# flash.net
KiCad netlist of a schematic drawn in Altium Designer
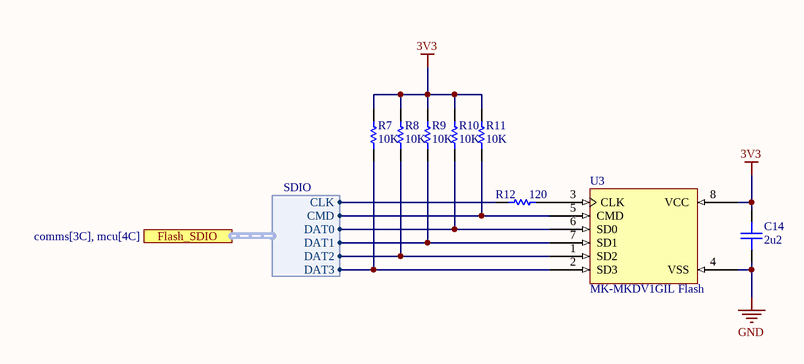
[diagram p0: flash.SchDoc]

(export (version "E")
  (design (tool "Eeschema 10.0.6"))
  (components
    (comp (ref "C14")
      (value "2u2")
      (description "Capacitor")
      (libsource (lib "drfc_schlib") (part "Capacitor"))
    )
    (comp (ref "R7") (value "10K") (description "Resistor") (libsource (lib "drfc_schlib") (part "Resistor")))
    (comp (ref "R8") (value "10K") (description "Resistor") (libsource (lib "drfc_schlib") (part "Resistor")))
    (comp (ref "R9") (value "10K") (description "Resistor") (libsource (lib "drfc_schlib") (part "Resistor")))
    (comp (ref "R10")
      (value "10K")
      (description "Resistor")
      (libsource (lib "drfc_schlib") (part "Resistor"))
    )
    (comp (ref "R11")
      (value "10K")
      (description "Resistor")
      (libsource (lib "drfc_schlib") (part "Resistor"))
    )
    (comp (ref "R12")
      (value "120")
      (description "Resistor")
      (libsource (lib "drfc_schlib") (part "Resistor"))
    )
    (comp (ref "U3")
      (value "MK-MKDV1GIL Flash")
      (description "1Gbit LGA-8(6x8) SD NAND FLASH ROHS")
      (libsource (lib "drfc_schlib") (part "MK-MKDV1GIL"))
    )
  )
  (nets
    (net (code "2") (name "/CLK") (class "Default")
      (node (ref "R12") (pin "2") (pinfunction "2_2") (pintype "passive"))
    )
    (net (code "3") (name "/CMD") (class "Default")
      (node (ref "R11") (pin "1") (pinfunction "1_1") (pintype "passive"))
      (node (ref "U3") (pin "5") (pinfunction "CMD_5") (pintype "input"))
    )
    (net (code "4") (name "/DAT0") (class "Default")
      (node (ref "R10") (pin "1") (pinfunction "1_1") (pintype "passive"))
      (node (ref "U3") (pin "6") (pinfunction "SD0_6") (pintype "input"))
    )
    (net (code "5") (name "/DAT1") (class "Default")
      (node (ref "R9") (pin "1") (pinfunction "1_1") (pintype "passive"))
      (node (ref "U3") (pin "7") (pinfunction "SD1_7") (pintype "input"))
    )
    (net (code "6") (name "/DAT2") (class "Default")
      (node (ref "R8") (pin "1") (pinfunction "1_1") (pintype "passive"))
      (node (ref "U3") (pin "1") (pinfunction "SD2_1") (pintype "input"))
    )
    (net (code "7") (name "/DAT3") (class "Default")
      (node (ref "R7") (pin "1") (pinfunction "1_1") (pintype "passive"))
      (node (ref "U3") (pin "2") (pinfunction "SD3_2") (pintype "input"))
    )
    (net (code "9") (name "3V3") (class "Default")
      (node (ref "C14") (pin "2") (pinfunction "2_2") (pintype "passive"))
      (node (ref "R10") (pin "2") (pinfunction "2_2") (pintype "passive"))
      (node (ref "R11") (pin "2") (pinfunction "2_2") (pintype "passive"))
      (node (ref "R7") (pin "2") (pinfunction "2_2") (pintype "passive"))
      (node (ref "R8") (pin "2") (pinfunction "2_2") (pintype "passive"))
      (node (ref "R9") (pin "2") (pinfunction "2_2") (pintype "passive"))
      (node (ref "U3") (pin "8") (pinfunction "VCC_8") (pintype "input"))
    )
    (net (code "10") (name "GND") (class "Default")
      (node (ref "C14") (pin "1") (pinfunction "1_1") (pintype "passive"))
      (node (ref "U3") (pin "4") (pinfunction "VSS_4") (pintype "input"))
    )
    (net (code "11") (name "Net-(U3-CLK)") (class "Default")
      (node (ref "R12") (pin "1") (pinfunction "1_1") (pintype "passive"))
      (node (ref "U3") (pin "3") (pinfunction "CLK_3") (pintype "input"))
    )
  )
)
